# C2LH_CAPE_B2B.net
KiCad netlist of a schematic drawn in Altium Designer
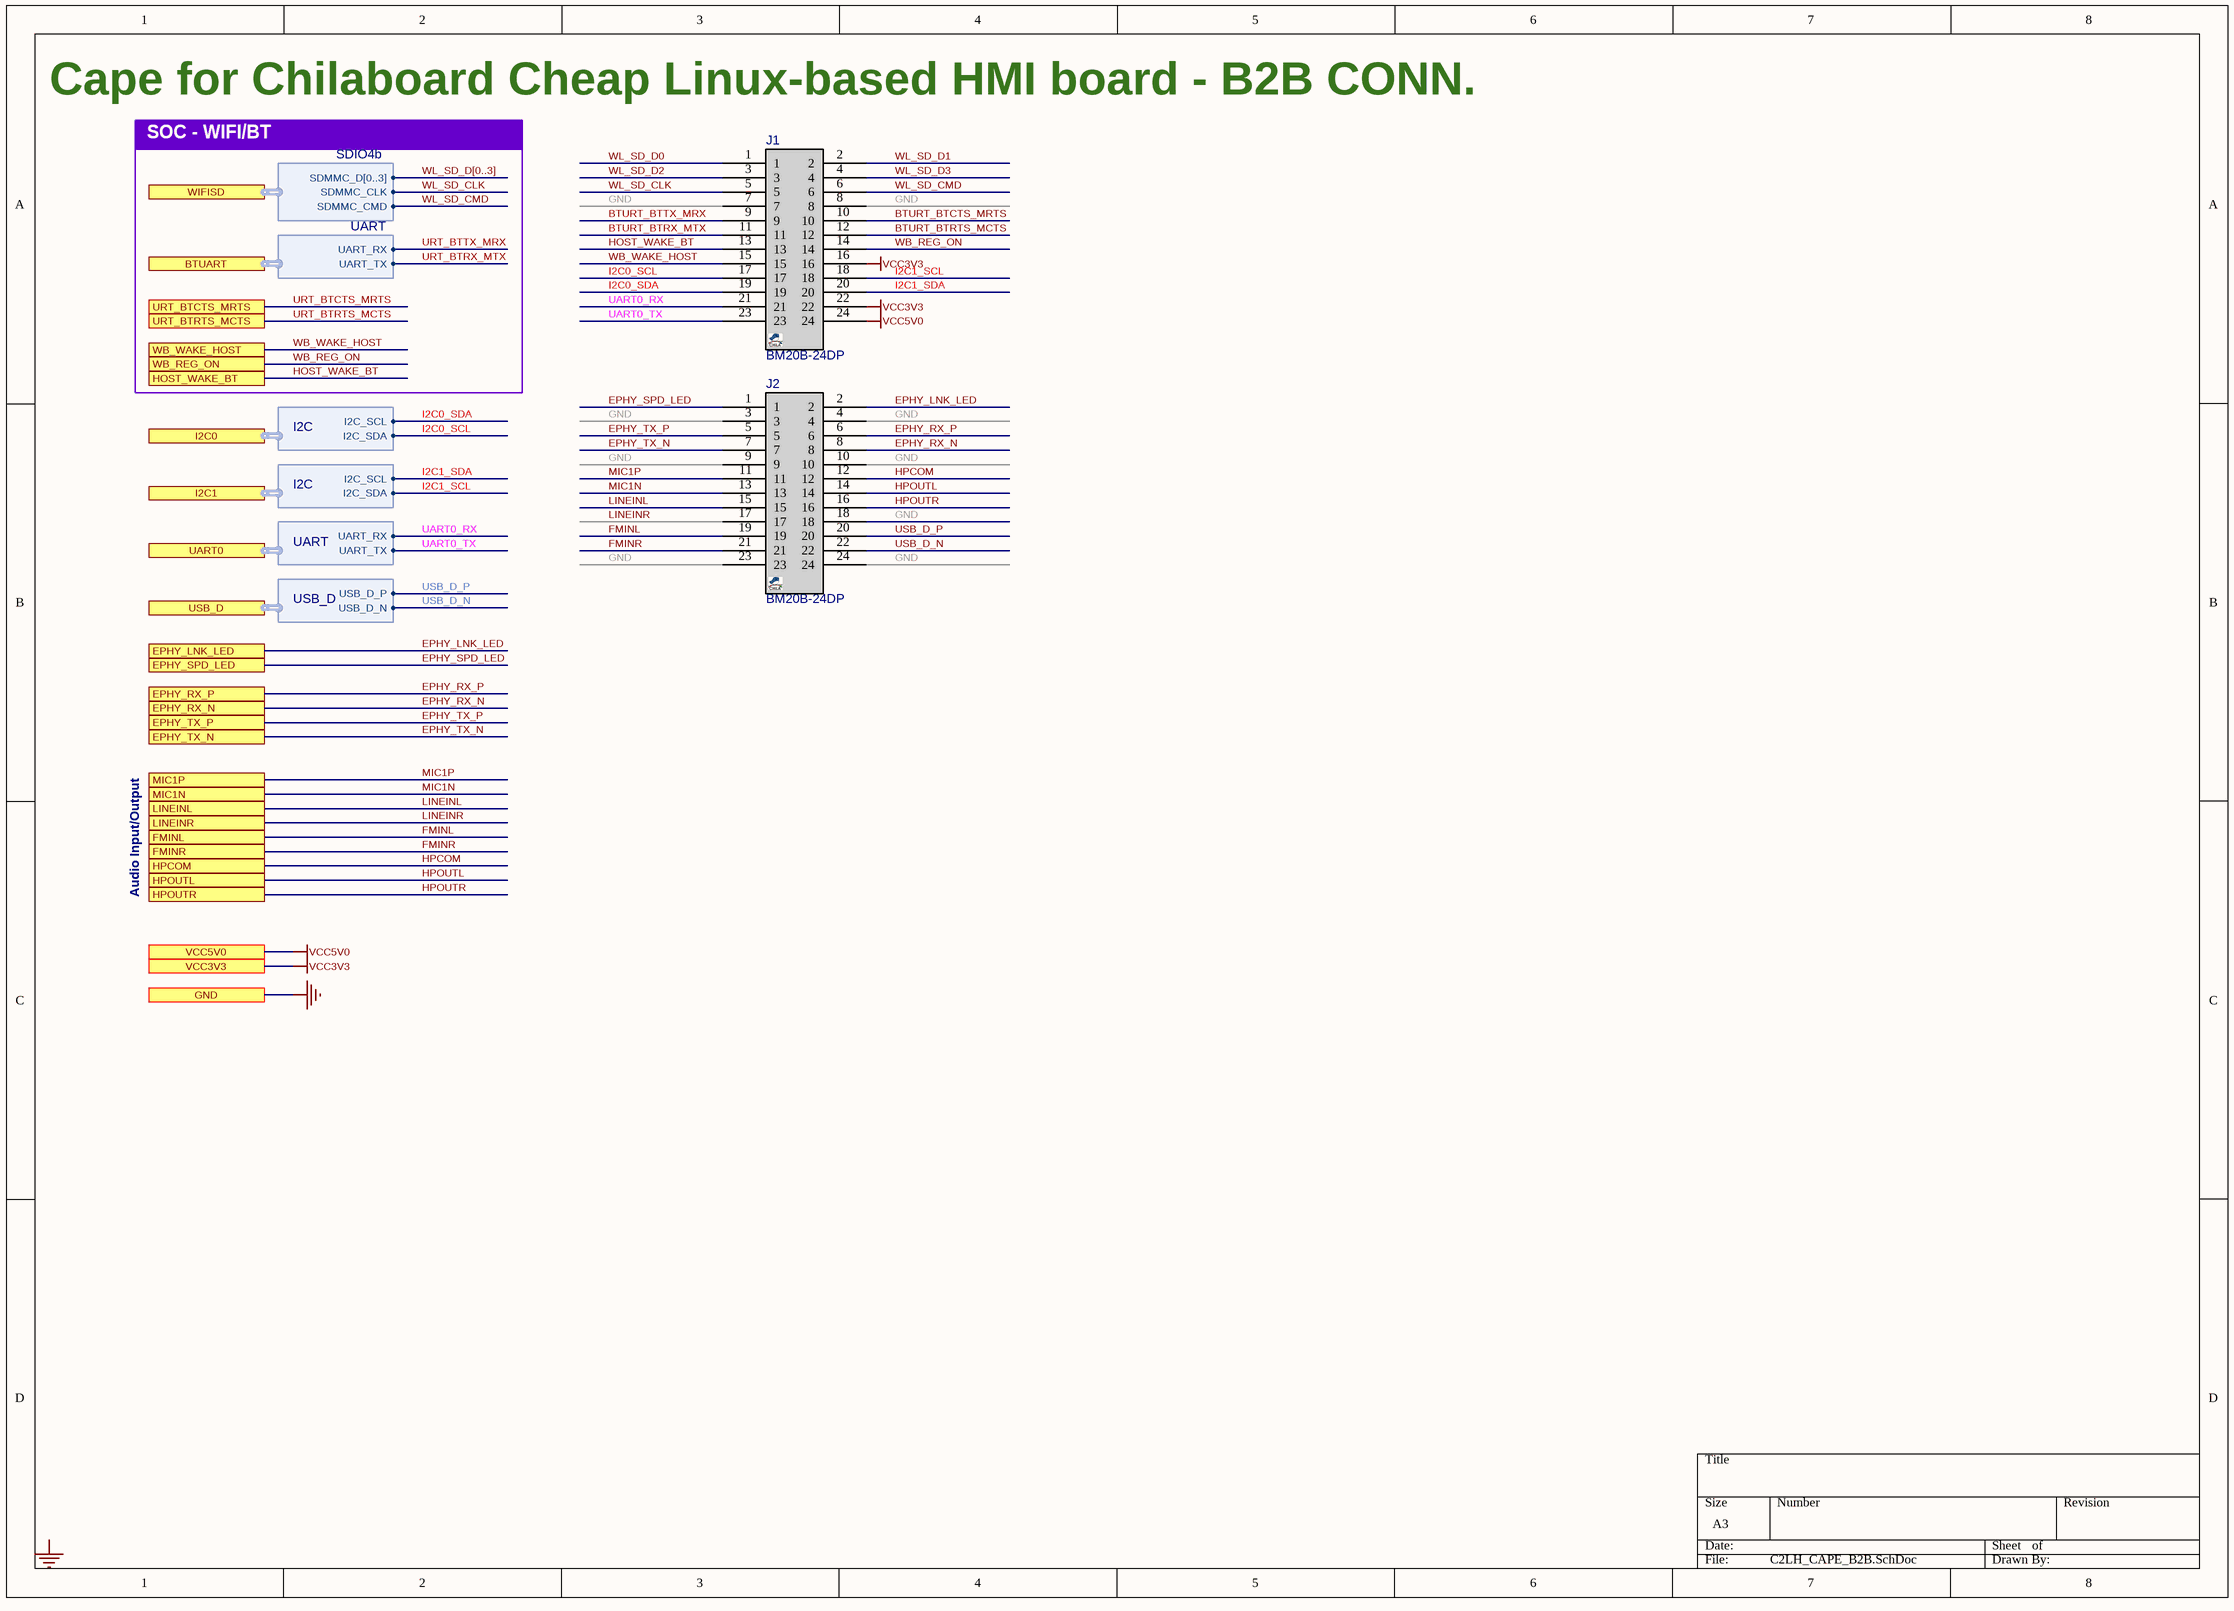
[diagram p0: C2LH_CAPE_B2B.SchDoc]

(export (version "E")
  (design (tool "Eeschema 10.0.6"))
  (components
    (comp (ref "J1")
      (value "BM20B-24DP")
      (footprint "BM20B_24DP")
      (description "DF23 Series B2B Connectors")
      (fields (field (name "MANF") "HIROSE") (field (name "MANF_P#") "BM20B(0.8)-24DP-0.4V(51)"))
      (libsource (lib "conn_b2b") (part "BM20B-24DP"))
    )
    (comp (ref "J2")
      (value "BM20B-24DP")
      (footprint "BM20B_24DP")
      (description "DF23 Series B2B Connectors")
      (fields (field (name "MANF") "HIROSE") (field (name "MANF_P#") "BM20B(0.8)-24DP-0.4V(51)"))
      (libsource (lib "conn_b2b") (part "BM20B-24DP"))
    )
  )
  (nets
    (net (code "5") (name "/BTURT_BTCTS_MRTS") (class "Default")
      (node (ref "J1") (pin "10") (pinfunction "10_10") (pintype "passive"))
    )
    (net (code "6") (name "/BTURT_BTRTS_MCTS") (class "Default")
      (node (ref "J1") (pin "12") (pinfunction "12_12") (pintype "passive"))
    )
    (net (code "7") (name "/BTURT_BTRX_MTX") (class "Default")
      (node (ref "J1") (pin "11") (pinfunction "11_11") (pintype "passive"))
    )
    (net (code "8") (name "/BTURT_BTTX_MRX") (class "Default")
      (node (ref "J1") (pin "9") (pinfunction "9_9") (pintype "passive"))
    )
    (net (code "9") (name "/EPHY_LNK_LED") (class "Default")
      (node (ref "J2") (pin "2") (pinfunction "2_2") (pintype "passive"))
    )
    (net (code "10") (name "/EPHY_RX_N") (class "Default")
      (node (ref "J2") (pin "8") (pinfunction "8_8") (pintype "passive"))
    )
    (net (code "11") (name "/EPHY_RX_P") (class "Default")
      (node (ref "J2") (pin "6") (pinfunction "6_6") (pintype "passive"))
    )
    (net (code "12") (name "/EPHY_SPD_LED") (class "Default")
      (node (ref "J2") (pin "1") (pinfunction "1_1") (pintype "passive"))
    )
    (net (code "13") (name "/EPHY_TX_N") (class "Default")
      (node (ref "J2") (pin "7") (pinfunction "7_7") (pintype "passive"))
    )
    (net (code "14") (name "/EPHY_TX_P") (class "Default")
      (node (ref "J2") (pin "5") (pinfunction "5_5") (pintype "passive"))
    )
    (net (code "15") (name "/FMINL") (class "Default")
      (node (ref "J2") (pin "19") (pinfunction "19_19") (pintype "passive"))
    )
    (net (code "16") (name "/FMINR") (class "Default")
      (node (ref "J2") (pin "21") (pinfunction "21_21") (pintype "passive"))
    )
    (net (code "17") (name "/HOST_WAKE_BT") (class "Default")
      (node (ref "J1") (pin "13") (pinfunction "13_13") (pintype "passive"))
    )
    (net (code "18") (name "/HPCOM") (class "Default")
      (node (ref "J2") (pin "12") (pinfunction "12_12") (pintype "passive"))
    )
    (net (code "19") (name "/HPOUTL") (class "Default")
      (node (ref "J2") (pin "14") (pinfunction "14_14") (pintype "passive"))
    )
    (net (code "20") (name "/HPOUTR") (class "Default")
      (node (ref "J2") (pin "16") (pinfunction "16_16") (pintype "passive"))
    )
    (net (code "21") (name "/I2C0_SCL") (class "Default")
      (node (ref "J1") (pin "17") (pinfunction "17_17") (pintype "passive"))
    )
    (net (code "22") (name "/I2C0_SDA") (class "Default")
      (node (ref "J1") (pin "19") (pinfunction "19_19") (pintype "passive"))
    )
    (net (code "23") (name "/I2C1_SCL") (class "Default")
      (node (ref "J1") (pin "18") (pinfunction "18_18") (pintype "passive"))
    )
    (net (code "24") (name "/I2C1_SDA") (class "Default")
      (node (ref "J1") (pin "20") (pinfunction "20_20") (pintype "passive"))
    )
    (net (code "25") (name "/LINEINL") (class "Default")
      (node (ref "J2") (pin "15") (pinfunction "15_15") (pintype "passive"))
    )
    (net (code "26") (name "/LINEINR") (class "Default")
      (node (ref "J2") (pin "17") (pinfunction "17_17") (pintype "passive"))
    )
    (net (code "27") (name "/MIC1N") (class "Default")
      (node (ref "J2") (pin "13") (pinfunction "13_13") (pintype "passive"))
    )
    (net (code "28") (name "/MIC1P") (class "Default")
      (node (ref "J2") (pin "11") (pinfunction "11_11") (pintype "passive"))
    )
    (net (code "29") (name "/UART0_RX") (class "Default")
      (node (ref "J1") (pin "21") (pinfunction "21_21") (pintype "passive"))
    )
    (net (code "30") (name "/UART0_TX") (class "Default")
      (node (ref "J1") (pin "23") (pinfunction "23_23") (pintype "passive"))
    )
    (net (code "35") (name "/USB_D_N") (class "Default")
      (node (ref "J2") (pin "22") (pinfunction "22_22") (pintype "passive"))
    )
    (net (code "36") (name "/USB_D_P") (class "Default")
      (node (ref "J2") (pin "20") (pinfunction "20_20") (pintype "passive"))
    )
    (net (code "37") (name "/WB_REG_ON") (class "Default")
      (node (ref "J1") (pin "14") (pinfunction "14_14") (pintype "passive"))
    )
    (net (code "38") (name "/WB_WAKE_HOST") (class "Default")
      (node (ref "J1") (pin "15") (pinfunction "15_15") (pintype "passive"))
    )
    (net (code "40") (name "/WL_SD_CLK") (class "Default")
      (node (ref "J1") (pin "5") (pinfunction "5_5") (pintype "passive"))
    )
    (net (code "41") (name "/WL_SD_CMD") (class "Default")
      (node (ref "J1") (pin "6") (pinfunction "6_6") (pintype "passive"))
    )
    (net (code "42") (name "/WL_SD_D0") (class "Default")
      (node (ref "J1") (pin "1") (pinfunction "1_1") (pintype "passive"))
    )
    (net (code "43") (name "/WL_SD_D1") (class "Default")
      (node (ref "J1") (pin "2") (pinfunction "2_2") (pintype "passive"))
    )
    (net (code "44") (name "/WL_SD_D2") (class "Default")
      (node (ref "J1") (pin "3") (pinfunction "3_3") (pintype "passive"))
    )
    (net (code "45") (name "/WL_SD_D3") (class "Default")
      (node (ref "J1") (pin "4") (pinfunction "4_4") (pintype "passive"))
    )
    (net (code "50") (name "GND") (class "Default")
      (node (ref "J1") (pin "7") (pinfunction "7_7") (pintype "passive"))
      (node (ref "J1") (pin "8") (pinfunction "8_8") (pintype "passive"))
      (node (ref "J2") (pin "10") (pinfunction "10_10") (pintype "passive"))
      (node (ref "J2") (pin "18") (pinfunction "18_18") (pintype "passive"))
      (node (ref "J2") (pin "23") (pinfunction "23_23") (pintype "passive"))
      (node (ref "J2") (pin "24") (pinfunction "24_24") (pintype "passive"))
      (node (ref "J2") (pin "3") (pinfunction "3_3") (pintype "passive"))
      (node (ref "J2") (pin "4") (pinfunction "4_4") (pintype "passive"))
      (node (ref "J2") (pin "9") (pinfunction "9_9") (pintype "passive"))
    )
    (net (code "51") (name "VCC3V3") (class "Default")
      (node (ref "J1") (pin "16") (pinfunction "16_16") (pintype "passive"))
      (node (ref "J1") (pin "22") (pinfunction "22_22") (pintype "passive"))
    )
    (net (code "52") (name "VCC5V0") (class "Default")
      (node (ref "J1") (pin "24") (pinfunction "24_24") (pintype "passive"))
    )
  )
)
